# UV_Watch_Pogo-1.net
KiCad netlist of a schematic drawn in Altium Designer
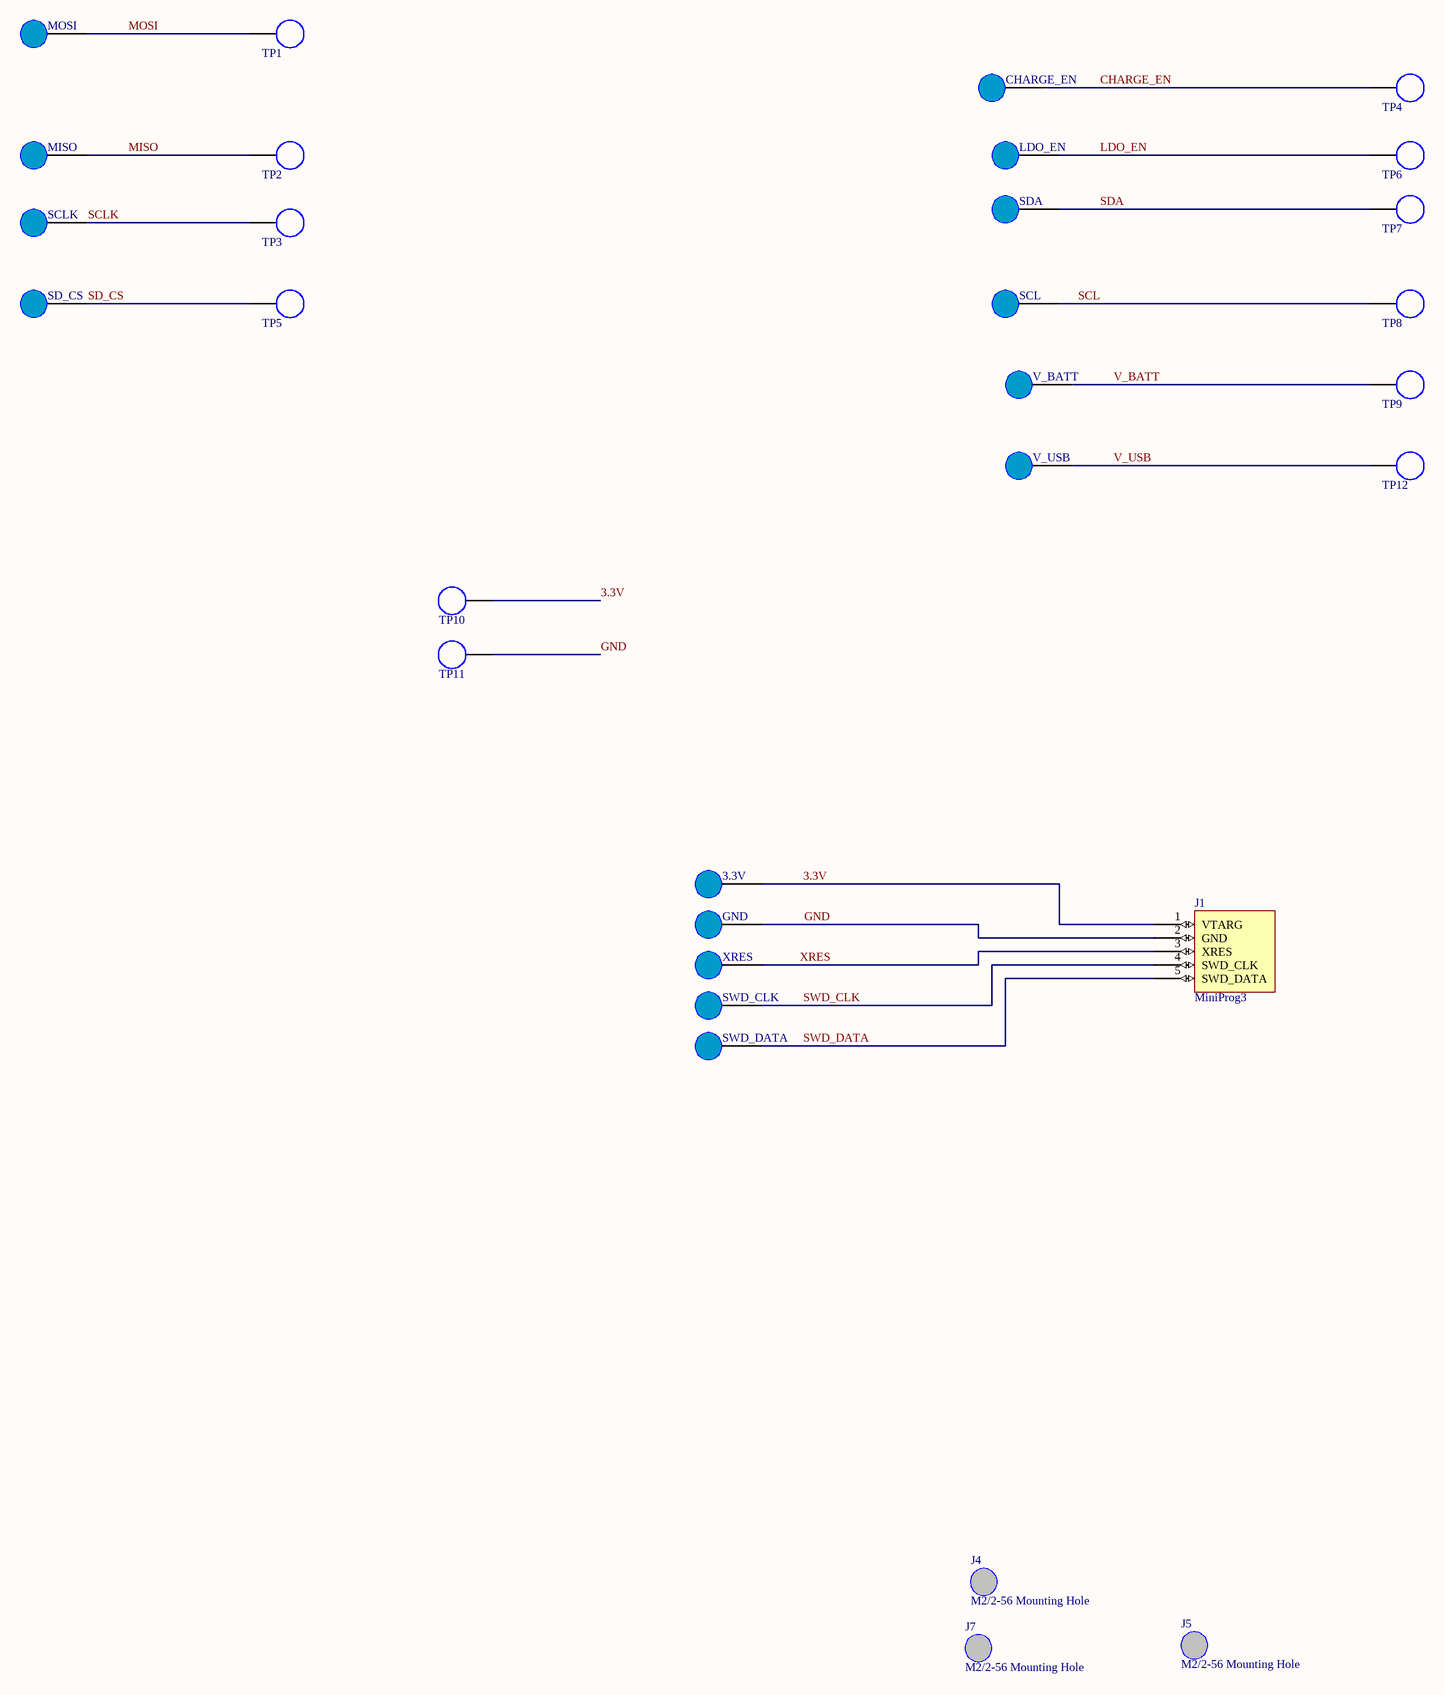
[diagram p0: UV_Watch_Pogo-1.SchDoc]

(export (version "E")
  (design (tool "Eeschema 10.0.6"))
  (components
    (comp (ref "3.3V")
      (value "Pogo-Pin Pad")
      (footprint "Pogo-Pin-Hole")
      (fields (field (name "MANUFACTURER") "Harwin") (field (name "MANUFACTURER PART NUMBER") "P13-2123"))
      (libsource (lib "UVS-Schlib") (part "Pogo-Pin Pad"))
    )
    (comp (ref "CHARGE_EN")
      (value "Pogo-Pin Pad")
      (footprint "Pogo-Pin-Hole")
      (fields (field (name "MANUFACTURER") "Harwin") (field (name "MANUFACTURER PART NUMBER") "P13-2123"))
      (libsource (lib "UVS-Schlib") (part "Pogo-Pin Pad"))
    )
    (comp (ref "GND")
      (value "Pogo-Pin Pad")
      (footprint "Pogo-Pin-Hole")
      (fields (field (name "MANUFACTURER") "Harwin") (field (name "MANUFACTURER PART NUMBER") "P13-2123"))
      (libsource (lib "UVS-Schlib") (part "Pogo-Pin Pad"))
    )
    (comp (ref "J1")
      (value "MiniProg3")
      (footprint "Header 5x1 8.5mm")
      (libsource (lib "UVS-Schlib") (part "MiniProg3"))
    )
    (comp (ref "J4")
      (value "M2/2-56 Mounting Hole")
      (footprint "Mounting Hole")
      (libsource (lib "UVS-Schlib") (part "M2/2-56 Mounting Hole"))
    )
    (comp (ref "J5")
      (value "M2/2-56 Mounting Hole")
      (footprint "Mounting Hole")
      (libsource (lib "UVS-Schlib") (part "M2/2-56 Mounting Hole"))
    )
    (comp (ref "J7")
      (value "M2/2-56 Mounting Hole")
      (footprint "Mounting Hole")
      (libsource (lib "UVS-Schlib") (part "M2/2-56 Mounting Hole"))
    )
    (comp (ref "LDO_EN")
      (value "Pogo-Pin Pad")
      (footprint "Pogo-Pin-Hole")
      (fields (field (name "MANUFACTURER") "Harwin") (field (name "MANUFACTURER PART NUMBER") "P13-2123"))
      (libsource (lib "UVS-Schlib") (part "Pogo-Pin Pad"))
    )
    (comp (ref "MISO")
      (value "Pogo-Pin Pad")
      (footprint "Pogo-Pin-Hole")
      (fields (field (name "MANUFACTURER") "Harwin") (field (name "MANUFACTURER PART NUMBER") "P13-2123"))
      (libsource (lib "UVS-Schlib") (part "Pogo-Pin Pad"))
    )
    (comp (ref "MOSI")
      (value "Pogo-Pin Pad")
      (footprint "Pogo-Pin-Hole")
      (fields (field (name "MANUFACTURER") "Harwin") (field (name "MANUFACTURER PART NUMBER") "P13-2123"))
      (libsource (lib "UVS-Schlib") (part "Pogo-Pin Pad"))
    )
    (comp (ref "SCL")
      (value "Pogo-Pin Pad")
      (footprint "Pogo-Pin-Hole")
      (fields (field (name "MANUFACTURER") "Harwin") (field (name "MANUFACTURER PART NUMBER") "P13-2123"))
      (libsource (lib "UVS-Schlib") (part "Pogo-Pin Pad"))
    )
    (comp (ref "SCLK")
      (value "Pogo-Pin Pad")
      (footprint "Pogo-Pin-Hole")
      (fields (field (name "MANUFACTURER") "Harwin") (field (name "MANUFACTURER PART NUMBER") "P13-2123"))
      (libsource (lib "UVS-Schlib") (part "Pogo-Pin Pad"))
    )
    (comp (ref "SDA")
      (value "Pogo-Pin Pad")
      (footprint "Pogo-Pin-Hole")
      (fields (field (name "MANUFACTURER") "Harwin") (field (name "MANUFACTURER PART NUMBER") "P13-2123"))
      (libsource (lib "UVS-Schlib") (part "Pogo-Pin Pad"))
    )
    (comp (ref "SD_CS")
      (value "Pogo-Pin Pad")
      (footprint "Pogo-Pin-Hole")
      (fields (field (name "MANUFACTURER") "Harwin") (field (name "MANUFACTURER PART NUMBER") "P13-2123"))
      (libsource (lib "UVS-Schlib") (part "Pogo-Pin Pad"))
    )
    (comp (ref "SWD_CLK")
      (value "Pogo-Pin Pad")
      (footprint "Pogo-Pin-Hole")
      (fields (field (name "MANUFACTURER") "Harwin") (field (name "MANUFACTURER PART NUMBER") "P13-2123"))
      (libsource (lib "UVS-Schlib") (part "Pogo-Pin Pad"))
    )
    (comp (ref "SWD_DATA")
      (value "Pogo-Pin Pad")
      (footprint "Pogo-Pin-Hole")
      (fields (field (name "MANUFACTURER") "Harwin") (field (name "MANUFACTURER PART NUMBER") "P13-2123"))
      (libsource (lib "UVS-Schlib") (part "Pogo-Pin Pad"))
    )
    (comp (ref "TP1")
      (value "S1751-46R")
      (footprint "S1751-46R")
      (description "PC TEST POINT TIN SMD")
      (fields (field (name "MANUFACTURER") "Harwin Inc."))
      (libsource (lib "UVS-Schlib") (part "S1751-46R"))
    )
    (comp (ref "TP2")
      (value "S1751-46R")
      (footprint "S1751-46R")
      (description "PC TEST POINT TIN SMD")
      (fields (field (name "MANUFACTURER") "Harwin Inc."))
      (libsource (lib "UVS-Schlib") (part "S1751-46R"))
    )
    (comp (ref "TP3")
      (value "S1751-46R")
      (footprint "S1751-46R")
      (description "PC TEST POINT TIN SMD")
      (fields (field (name "MANUFACTURER") "Harwin Inc."))
      (libsource (lib "UVS-Schlib") (part "S1751-46R"))
    )
    (comp (ref "TP4")
      (value "S1751-46R")
      (footprint "S1751-46R")
      (description "PC TEST POINT TIN SMD")
      (fields (field (name "MANUFACTURER") "Harwin Inc."))
      (libsource (lib "UVS-Schlib") (part "S1751-46R"))
    )
    (comp (ref "TP5")
      (value "S1751-46R")
      (footprint "S1751-46R")
      (description "PC TEST POINT TIN SMD")
      (fields (field (name "MANUFACTURER") "Harwin Inc."))
      (libsource (lib "UVS-Schlib") (part "S1751-46R"))
    )
    (comp (ref "TP6")
      (value "S1751-46R")
      (footprint "S1751-46R")
      (description "PC TEST POINT TIN SMD")
      (fields (field (name "MANUFACTURER") "Harwin Inc."))
      (libsource (lib "UVS-Schlib") (part "S1751-46R"))
    )
    (comp (ref "TP7")
      (value "S1751-46R")
      (footprint "S1751-46R")
      (description "PC TEST POINT TIN SMD")
      (fields (field (name "MANUFACTURER") "Harwin Inc."))
      (libsource (lib "UVS-Schlib") (part "S1751-46R"))
    )
    (comp (ref "TP8")
      (value "S1751-46R")
      (footprint "S1751-46R")
      (description "PC TEST POINT TIN SMD")
      (fields (field (name "MANUFACTURER") "Harwin Inc."))
      (libsource (lib "UVS-Schlib") (part "S1751-46R"))
    )
    (comp (ref "TP9")
      (value "S1751-46R")
      (footprint "S1751-46R")
      (description "PC TEST POINT TIN SMD")
      (fields (field (name "MANUFACTURER") "Harwin Inc."))
      (libsource (lib "UVS-Schlib") (part "S1751-46R"))
    )
    (comp (ref "TP10")
      (value "S1751-46R")
      (footprint "S1751-46R")
      (description "PC TEST POINT TIN SMD")
      (fields (field (name "MANUFACTURER") "Harwin Inc."))
      (libsource (lib "UVS-Schlib") (part "S1751-46R"))
    )
    (comp (ref "TP11")
      (value "S1751-46R")
      (footprint "S1751-46R")
      (description "PC TEST POINT TIN SMD")
      (fields (field (name "MANUFACTURER") "Harwin Inc."))
      (libsource (lib "UVS-Schlib") (part "S1751-46R"))
    )
    (comp (ref "TP12")
      (value "S1751-46R")
      (footprint "S1751-46R")
      (description "PC TEST POINT TIN SMD")
      (fields (field (name "MANUFACTURER") "Harwin Inc."))
      (libsource (lib "UVS-Schlib") (part "S1751-46R"))
    )
    (comp (ref "V_BATT")
      (value "Pogo-Pin Pad")
      (footprint "Pogo-Pin-Hole")
      (fields (field (name "MANUFACTURER") "Harwin") (field (name "MANUFACTURER PART NUMBER") "P13-2123"))
      (libsource (lib "UVS-Schlib") (part "Pogo-Pin Pad"))
    )
    (comp (ref "V_USB")
      (value "Pogo-Pin Pad")
      (footprint "Pogo-Pin-Hole")
      (fields (field (name "MANUFACTURER") "Harwin") (field (name "MANUFACTURER PART NUMBER") "P13-2123"))
      (libsource (lib "UVS-Schlib") (part "Pogo-Pin Pad"))
    )
    (comp (ref "XRES")
      (value "Pogo-Pin Pad")
      (footprint "Pogo-Pin-Hole")
      (fields (field (name "MANUFACTURER") "Harwin") (field (name "MANUFACTURER PART NUMBER") "P13-2123"))
      (libsource (lib "UVS-Schlib") (part "Pogo-Pin Pad"))
    )
  )
  (nets
    (net (code "1") (name "/3.3V") (class "Default")
      (node (ref "3.3V") (pin "1") (pinfunction "1_1") (pintype "passive"))
      (node (ref "J1") (pin "1") (pinfunction "VTARG_1") (pintype "bidirectional"))
      (node (ref "TP10") (pin "1") (pinfunction "1_1") (pintype "passive"))
    )
    (net (code "2") (name "/CHARGE_EN") (class "Default")
      (node (ref "CHARGE_EN") (pin "1") (pinfunction "1_1") (pintype "passive"))
      (node (ref "TP4") (pin "1") (pinfunction "1_1") (pintype "passive"))
    )
    (net (code "3") (name "/GND") (class "Default")
      (node (ref "GND") (pin "1") (pinfunction "1_1") (pintype "passive"))
      (node (ref "J1") (pin "2") (pinfunction "GND_2") (pintype "bidirectional"))
      (node (ref "TP11") (pin "1") (pinfunction "1_1") (pintype "passive"))
    )
    (net (code "4") (name "/LDO_EN") (class "Default")
      (node (ref "LDO_EN") (pin "1") (pinfunction "1_1") (pintype "passive"))
      (node (ref "TP6") (pin "1") (pinfunction "1_1") (pintype "passive"))
    )
    (net (code "5") (name "/MISO") (class "Default")
      (node (ref "MISO") (pin "1") (pinfunction "1_1") (pintype "passive"))
      (node (ref "TP2") (pin "1") (pinfunction "1_1") (pintype "passive"))
    )
    (net (code "6") (name "/MOSI") (class "Default")
      (node (ref "MOSI") (pin "1") (pinfunction "1_1") (pintype "passive"))
      (node (ref "TP1") (pin "1") (pinfunction "1_1") (pintype "passive"))
    )
    (net (code "7") (name "/SCL") (class "Default")
      (node (ref "SCL") (pin "1") (pinfunction "1_1") (pintype "passive"))
      (node (ref "TP8") (pin "1") (pinfunction "1_1") (pintype "passive"))
    )
    (net (code "8") (name "/SCLK") (class "Default")
      (node (ref "SCLK") (pin "1") (pinfunction "1_1") (pintype "passive"))
      (node (ref "TP3") (pin "1") (pinfunction "1_1") (pintype "passive"))
    )
    (net (code "9") (name "/SDA") (class "Default")
      (node (ref "SDA") (pin "1") (pinfunction "1_1") (pintype "passive"))
      (node (ref "TP7") (pin "1") (pinfunction "1_1") (pintype "passive"))
    )
    (net (code "10") (name "/SD_CS") (class "Default")
      (node (ref "SD_CS") (pin "1") (pinfunction "1_1") (pintype "passive"))
      (node (ref "TP5") (pin "1") (pinfunction "1_1") (pintype "passive"))
    )
    (net (code "11") (name "/SWD_CLK") (class "Default")
      (node (ref "J1") (pin "4") (pinfunction "SWD_CLK_4") (pintype "bidirectional"))
      (node (ref "SWD_CLK") (pin "1") (pinfunction "1_1") (pintype "passive"))
    )
    (net (code "12") (name "/SWD_DATA") (class "Default")
      (node (ref "J1") (pin "5") (pinfunction "SWD_DATA_5") (pintype "bidirectional"))
      (node (ref "SWD_DATA") (pin "1") (pinfunction "1_1") (pintype "passive"))
    )
    (net (code "13") (name "/V_BATT") (class "Default")
      (node (ref "TP9") (pin "1") (pinfunction "1_1") (pintype "passive"))
      (node (ref "V_BATT") (pin "1") (pinfunction "1_1") (pintype "passive"))
    )
    (net (code "14") (name "/V_USB") (class "Default")
      (node (ref "TP12") (pin "1") (pinfunction "1_1") (pintype "passive"))
      (node (ref "V_USB") (pin "1") (pinfunction "1_1") (pintype "passive"))
    )
    (net (code "15") (name "/XRES") (class "Default")
      (node (ref "J1") (pin "3") (pinfunction "XRES_3") (pintype "bidirectional"))
      (node (ref "XRES") (pin "1") (pinfunction "1_1") (pintype "passive"))
    )
  )
)
